# 5V-REG.net
KiCad netlist of a schematic drawn in Altium Designer
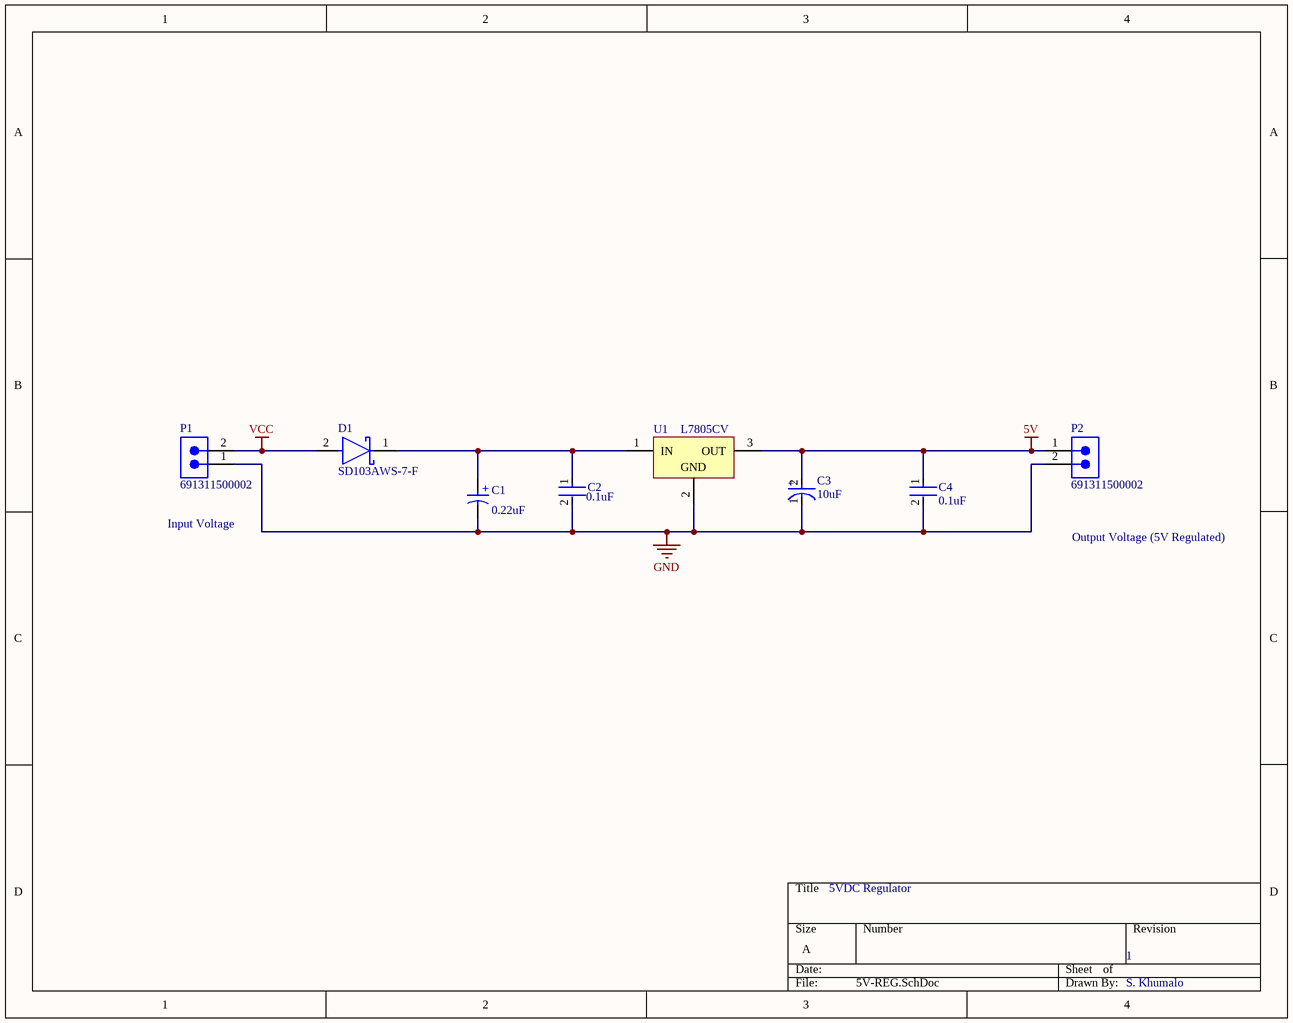
[diagram p0: 5V-REG.SchDoc]

(export (version "E")
  (design (tool "Eeschema 10.0.6"))
  (components
    (comp (ref "C1")
      (value "0.22uF")
      (footprint "WCAP-ATG8_D5H11")
      (description "860010772002 WCAP-ATG8 Aluminum Electrolytic Capacitors")
      (fields (field (name "TOLERANCE") "20%"))
      (libsource (lib "Altium Content Vault") (part "Capacitor_Polarized"))
    )
    (comp (ref "C2")
      (value "0.1uF")
      (footprint "FP-RDE0P1-MFG")
      (description "Ceramic Capacitor 100nF ±10% 25V X7R Radial")
      (fields (field (name "TOLERANCE") "10%"))
      (libsource (lib "Altium Content Vault") (part "b4654b650e69147ec39a6b967a45e02"))
    )
    (comp (ref "C3")
      (value "10uF")
      (footprint "FP-RAD-TH-D_5_0_5-L_11_1-MFG")
      (description "Aluminum Electrolytic Capacitors (Radial Lead Type) 10uF ±20% 50V")
      (fields (field (name "TOLERANCE") "20%") (field (name "VOLTAGE") "50V"))
      (libsource (lib "Altium Content Vault") (part "a00bbbee19879c290e62620ae7e47b1"))
    )
    (comp (ref "C4")
      (value "0.1uF")
      (footprint "FP-RDE0P1-MFG")
      (description "Ceramic Capacitor 100nF ±10% 25V X7R Radial")
      (fields (field (name "TOLERANCE") "10%"))
      (libsource (lib "Altium Content Vault") (part "b4654b650e69147ec39a6b967a45e02"))
    )
    (comp (ref "D1")
      (value "SD103AWS-7-F")
      (footprint "FP-SOD323-MFG")
      (description "DIODE SCHOTTKY 40V 350MA SOD323")
      (fields
        (field (name "OCTOPART") "https://octopart.com/sd103aws-7-f-diodes+inc.-55389602")
        (field (name "MANUFACTURER") "Diodes Inc.")
      )
      (libsource (lib "Altium Content Vault") (part "1d6ec82d83fb6aee721767c19dac4b9"))
    )
    (comp (ref "P1")
      (value "691311500002")
      (footprint "691311500002")
      (fields (field (name "VOLTAGE") "300V"))
      (libsource (lib "Altium Content Vault") (part "TBL - 1R - 02P - Male"))
    )
    (comp (ref "P2")
      (value "691311500002")
      (footprint "691311500002")
      (fields (field (name "VOLTAGE") "300V"))
      (libsource (lib "Altium Content Vault") (part "TBL - 1R - 02P - Male"))
    )
    (comp (ref "U1")
      (value "L7805CV")
      (footprint "TO220")
      (description "Positive Voltage Regulator, 5V, 3-Pin TO-220")
      (libsource (lib "Altium Content Vault") (part "PM-REG-L4940-SIL3"))
    )
  )
  (nets
    (net (code "1") (name "5V") (class "Default")
      (node (ref "C3") (pin "2") (pinfunction "A_2") (pintype "passive"))
      (node (ref "C4") (pin "1") (pinfunction "1_1") (pintype "passive"))
      (node (ref "P2") (pin "1") (pinfunction "1_1") (pintype "passive"))
      (node (ref "U1") (pin "3") (pinfunction "OUT_3") (pintype "power_in"))
    )
    (net (code "2") (name "GND") (class "Default")
      (node (ref "C1") (pin "2") (pinfunction "N_2") (pintype "passive"))
      (node (ref "C2") (pin "2") (pinfunction "2_2") (pintype "passive"))
      (node (ref "C3") (pin "1") (pinfunction "C_1") (pintype "passive"))
      (node (ref "C4") (pin "2") (pinfunction "2_2") (pintype "passive"))
      (node (ref "P1") (pin "1") (pinfunction "1_1") (pintype "passive"))
      (node (ref "P2") (pin "2") (pinfunction "2_2") (pintype "passive"))
      (node (ref "U1") (pin "2") (pinfunction "GND_2") (pintype "power_in"))
    )
    (net (code "3") (name "Net-(C1-P)") (class "Default")
      (node (ref "C1") (pin "1") (pinfunction "P_1") (pintype "passive"))
      (node (ref "C2") (pin "1") (pinfunction "1_1") (pintype "passive"))
      (node (ref "D1") (pin "1") (pinfunction "C_1") (pintype "passive"))
      (node (ref "U1") (pin "1") (pinfunction "IN_1") (pintype "power_in"))
    )
    (net (code "4") (name "VCC") (class "Default")
      (node (ref "D1") (pin "2") (pinfunction "A_2") (pintype "passive"))
      (node (ref "P1") (pin "2") (pinfunction "2_2") (pintype "passive"))
    )
  )
)
